# P02_Processor_1_of_3_JTAG_Header.net
KiCad netlist of a schematic drawn in Altium Designer
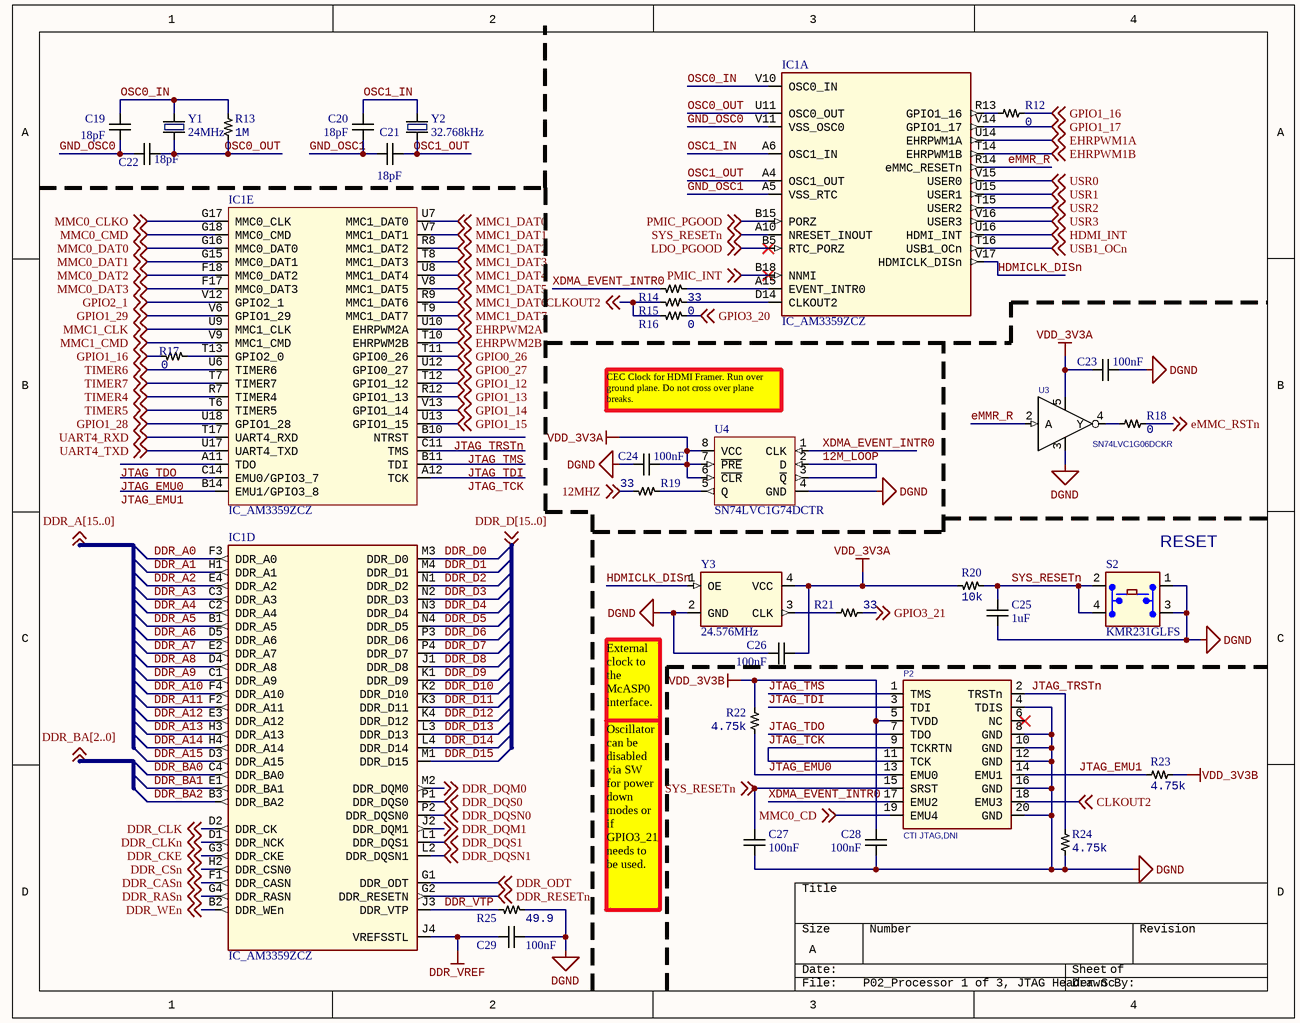
[diagram p0: P02_Processor 1 of 3, JTAG Header.SchDoc]

(export (version "E")
  (design (tool "Eeschema 10.0.6"))
  (components
    (comp (ref "C19")
      (value "CC0402JRNPO9BN180")
      (footprint "CAP0402")
      (description "MLCC 18pF 0402 SMD")
      (fields
        (field (name "MANUFACTURER") "Yageo")
        (field (name "CAPACITANCE") "18pF")
        (field (name "TOLERANCE") "5%")
      )
      (libsource (lib "Orient2") (part "CAP_18pF"))
    )
    (comp (ref "C20")
      (value "CC0402JRNPO9BN180")
      (footprint "CAP0402")
      (description "MLCC 18pF 0402 SMD")
      (fields
        (field (name "MANUFACTURER") "Yageo")
        (field (name "CAPACITANCE") "18pF")
        (field (name "TOLERANCE") "5%")
      )
      (libsource (lib "Orient2") (part "CAP_18pF"))
    )
    (comp (ref "C21")
      (value "CC0402JRNPO9BN180")
      (footprint "CAP0402")
      (description "MLCC 18pF 0402 SMD")
      (fields
        (field (name "MANUFACTURER") "Yageo")
        (field (name "CAPACITANCE") "18pF")
        (field (name "TOLERANCE") "5%")
      )
      (libsource (lib "Orient2") (part "CAP_18pF"))
    )
    (comp (ref "C22")
      (value "CC0402JRNPO9BN180")
      (footprint "CAP0402")
      (description "MLCC 18pF 0402 SMD")
      (fields
        (field (name "MANUFACTURER") "Yageo")
        (field (name "CAPACITANCE") "18pF")
        (field (name "TOLERANCE") "5%")
      )
      (libsource (lib "Orient2") (part "CAP_18pF"))
    )
    (comp (ref "C23")
      (value "C0402C104K4RACTU")
      (footprint "CAP0402")
      (description "MLCC 100nF 0402 SMD")
      (fields
        (field (name "MANUFACTURER") "KEMET")
        (field (name "TOLERANCE") "10%")
        (field (name "CAPACITANCE") "100nF")
      )
      (libsource (lib "Orient2") (part "CAP_100nF"))
    )
    (comp (ref "C24")
      (value "C0402C104K4RACTU")
      (footprint "CAP0402")
      (description "MLCC 100nF 0402 SMD")
      (fields
        (field (name "MANUFACTURER") "KEMET")
        (field (name "TOLERANCE") "10%")
        (field (name "CAPACITANCE") "100nF")
      )
      (libsource (lib "Orient2") (part "CAP_100nF"))
    )
    (comp (ref "C25")
      (value "CC0402KRX5R6BB105")
      (footprint "CAP0402")
      (description "MLCC 1uF 0402 SMD")
      (fields
        (field (name "CAPACITANCE") "1uF")
        (field (name "MANUFACTURER") "Yageo")
        (field (name "TOLERANCE") "10%")
      )
      (libsource (lib "Orient2") (part "CAP_1uF"))
    )
    (comp (ref "C26")
      (value "C0402C104K4RACTU")
      (footprint "CAP0402")
      (description "MLCC 100nF 0402 SMD")
      (fields
        (field (name "MANUFACTURER") "KEMET")
        (field (name "TOLERANCE") "10%")
        (field (name "CAPACITANCE") "100nF")
      )
      (libsource (lib "Orient2") (part "CAP_100nF"))
    )
    (comp (ref "C27")
      (value "C0402C104K4RACTU")
      (footprint "CAP0402")
      (description "MLCC 100nF 0402 SMD")
      (fields
        (field (name "MANUFACTURER") "KEMET")
        (field (name "TOLERANCE") "10%")
        (field (name "CAPACITANCE") "100nF")
      )
      (libsource (lib "Orient2") (part "CAP_100nF"))
    )
    (comp (ref "C28")
      (value "C0402C104K4RACTU")
      (footprint "CAP0402")
      (description "MLCC 100nF 0402 SMD")
      (fields
        (field (name "MANUFACTURER") "KEMET")
        (field (name "TOLERANCE") "10%")
        (field (name "CAPACITANCE") "100nF")
      )
      (libsource (lib "Orient2") (part "CAP_100nF"))
    )
    (comp (ref "C29")
      (value "C0402C104K4RACTU")
      (footprint "CAP0402")
      (description "MLCC 100nF 0402 SMD")
      (fields
        (field (name "MANUFACTURER") "KEMET")
        (field (name "TOLERANCE") "10%")
        (field (name "CAPACITANCE") "100nF")
      )
      (libsource (lib "Orient2") (part "CAP_100nF"))
    )
    (comp (ref "IC1")
      (value "IC_AM3359ZCZ")
      (footprint "BGA-324")
      (description "SubArctic Cortex A8 Processor 18x18")
      (fields
        (field (name "MANUFACTURER") "Texas Instruments")
        (field (name "MANUFACTURER PART NUMBER") "XAM3359ZCZ")
      )
      (libsource (lib "Orient2") (part "IC_AM335X_ZCE_1"))
    )
    (comp (ref "P2")
      (value "CTI JTAG,DNI")
      (description "Dual Line Header 10x2pin Tin")
      (fields
        (field (name "MANUFACTURER") "Samtec Inc")
        (field (name "MANUFACTURER PART NUMBER") "FTR-110-03-G-D-06")
      )
      (libsource (lib "Orient2") (part "HDR_10x2_CJTAG"))
    )
    (comp (ref "R12")
      (value "RC0402JR-070RL")
      (footprint "RES0402")
      (description "Resistor 0Ohm 0402 SMD")
      (fields
        (field (name "MANUFACTURER") "Yageo")
        (field (name "TOLERANCE") "5%")
        (field (name "RESISTANCE") "0")
      )
      (libsource (lib "Orient2") (part "RES_0"))
    )
    (comp (ref "R13")
      (value "RC0402FR-071ML")
      (footprint "RES0402")
      (description "Resistor 1MOhm 0402 SMD")
      (fields
        (field (name "MANUFACTURER") "Yageo")
        (field (name "TOLERANCE") "1%")
        (field (name "RESISTANCE") "1M")
      )
      (libsource (lib "Orient2") (part "RES_1M"))
    )
    (comp (ref "R14")
      (value "RC0402FR-0733RL")
      (footprint "RES0402")
      (description "Resistor 33Ohm 0402 SMD")
      (fields
        (field (name "MANUFACTURER") "Yageo")
        (field (name "TOLERANCE") "1%")
        (field (name "RESISTANCE") "33")
      )
      (libsource (lib "Orient2") (part "RES_33"))
    )
    (comp (ref "R15")
      (value "RC0402JR-070RL")
      (footprint "RES0402")
      (description "Resistor 0Ohm 0402 SMD")
      (fields
        (field (name "MANUFACTURER") "Yageo")
        (field (name "TOLERANCE") "5%")
        (field (name "RESISTANCE") "0")
      )
      (libsource (lib "Orient2") (part "RES_0"))
    )
    (comp (ref "R16")
      (value "RC0402JR-070RL")
      (footprint "RES0402")
      (description "Resistor 0Ohm 0402 SMD")
      (fields
        (field (name "MANUFACTURER") "Yageo")
        (field (name "TOLERANCE") "5%")
        (field (name "RESISTANCE") "0")
      )
      (libsource (lib "Orient2") (part "RES_0"))
    )
    (comp (ref "R17")
      (value "RC0402JR-070RL")
      (footprint "RES0402")
      (description "Resistor 0Ohm 0402 SMD")
      (fields
        (field (name "MANUFACTURER") "Yageo")
        (field (name "TOLERANCE") "5%")
        (field (name "RESISTANCE") "0")
      )
      (libsource (lib "Orient2") (part "RES_0"))
    )
    (comp (ref "R18")
      (value "RC0402JR-070RL")
      (footprint "RES0402")
      (description "Resistor 0Ohm 0402 SMD")
      (fields
        (field (name "MANUFACTURER") "Yageo")
        (field (name "TOLERANCE") "5%")
        (field (name "RESISTANCE") "0")
      )
      (libsource (lib "Orient2") (part "RES_0"))
    )
    (comp (ref "R19")
      (value "RC0402FR-0733RL")
      (footprint "RES0402")
      (description "Resistor 33Ohm 0402 SMD")
      (fields
        (field (name "MANUFACTURER") "Yageo")
        (field (name "TOLERANCE") "1%")
        (field (name "RESISTANCE") "33")
      )
      (libsource (lib "Orient2") (part "RES_33"))
    )
    (comp (ref "R20")
      (value "RC0402FR-0710KL")
      (footprint "RES0402")
      (description "Resistor 10kOhm 0402 SMD")
      (fields
        (field (name "MANUFACTURER") "Yageo")
        (field (name "TOLERANCE") "1%")
        (field (name "RESISTANCE") "10k")
      )
      (libsource (lib "Orient2") (part "RES_10k"))
    )
    (comp (ref "R21")
      (value "RC0402FR-0733RL")
      (footprint "RES0402")
      (description "Resistor 33Ohm 0402 SMD")
      (fields
        (field (name "MANUFACTURER") "Yageo")
        (field (name "TOLERANCE") "1%")
        (field (name "RESISTANCE") "33")
      )
      (libsource (lib "Orient2") (part "RES_33"))
    )
    (comp (ref "R22")
      (value "RC0402FR-074K75L")
      (footprint "RES0402")
      (description "Resistor 4.75kOhm 0402 SMD")
      (fields
        (field (name "MANUFACTURER") "Yageo")
        (field (name "TOLERANCE") "1%")
        (field (name "RESISTANCE") "4.75k")
      )
      (libsource (lib "Orient2") (part "RES_4.75k"))
    )
    (comp (ref "R23")
      (value "RC0402FR-074K75L")
      (footprint "RES0402")
      (description "Resistor 4.75kOhm 0402 SMD")
      (fields
        (field (name "MANUFACTURER") "Yageo")
        (field (name "TOLERANCE") "1%")
        (field (name "RESISTANCE") "4.75k")
      )
      (libsource (lib "Orient2") (part "RES_4.75k"))
    )
    (comp (ref "R24")
      (value "RC0402FR-074K75L")
      (footprint "RES0402")
      (description "Resistor 4.75kOhm 0402 SMD")
      (fields
        (field (name "MANUFACTURER") "Yageo")
        (field (name "TOLERANCE") "1%")
        (field (name "RESISTANCE") "4.75k")
      )
      (libsource (lib "Orient2") (part "RES_4.75k"))
    )
    (comp (ref "R25")
      (value "RC0402FR-0749R9")
      (footprint "RES0402")
      (description "Resistor 49.9Ohm 0402 SMD")
      (fields
        (field (name "MANUFACTURER") "Yageo")
        (field (name "MANUFACTURER PART NUMBER") "RC0402FR-0749R9L")
        (field (name "RESISTANCE") "49.9")
      )
      (libsource (lib "Orient2") (part "RES_49.9"))
    )
    (comp (ref "S2")
      (value "KMR231GLFS")
      (footprint "SW4SMD_63X161LS")
      (description "Microminiature Tact Switch for SMT")
      (fields (field (name "MANUFACTURER") "C&K Components"))
      (libsource (lib "Orient2") (part "KMR2"))
    )
    (comp (ref "U3")
      (value "SN74LVC1G06DCKR")
      (footprint "SC70_DCK")
      (description "IC INVERTER SINGLE 1INPUT SC705")
      (fields
        (field (name "MANUFACTURER") "Texas Instruments")
        (field (name "MANUFACTURER PART NUMBER") "SN74LVC1G06DCKTG4")
      )
      (libsource (lib "Orient2") (part "IC_Inverter"))
    )
    (comp (ref "U4")
      (value "SN74LVC1G74DCTR")
      (footprint "VSSOP-8")
      (description "SINGLE  POSITIVE-EDGE-TRIGGERED  D-TYPE  FLIP-FLOP WITH  CLEAR  AND  PRESET")
      (fields (field (name "MANUFACTURER") "Texas Instruments"))
      (libsource (lib "Orient2") (part "SN74LVC1G74DCTR"))
    )
    (comp (ref "Y1")
      (value "24MHz")
      (footprint "XTAL150SMD_125X196")
      (description "CRYSTAL 24.000MHZ 18PF SMD")
      (fields
        (field (name "MANUFACTURER") "TXC CORPORATION")
        (field (name "MANUFACTURER PART NUMBER") "7A-24.000MAAJ-T")
      )
      (libsource (lib "Orient2") (part "CRYS_24MHz_SCC"))
    )
    (comp (ref "Y2")
      (value "32.768kHz")
      (footprint "SOJ-4")
      (description "CRYSTAL 32.768KHZ 12.5PF SMD")
      (fields
        (field (name "MANUFACTURER") "Citizen Finetech Miyota")
        (field (name "MANUFACTURER PART NUMBER") "CM200C-32.768KAZF-UT")
      )
      (libsource (lib "Orient2") (part "CRYS_32.768kHz"))
    )
    (comp (ref "Y3")
      (value "24.576MHz")
      (footprint "OSC4_61X65LS_79X98SMD")
      (fields
        (field (name "MANUFACTURER") "Abracon Corporation")
        (field (name "MANUFACTURER PART NUMBER") "ASDMB-24.576MHZ-LC-T")
      )
      (libsource (lib "Orient2") (part "ASDMB"))
    )
  )
  (nets
    (net (code "1") (name "/12M_LOOP") (class "Default")
      (node (ref "U4") (pin "2") (pinfunction "D_2") (pintype "input"))
      (node (ref "U4") (pin "3") (pinfunction "~{Q}_3") (pintype "output"))
    )
    (net (code "2") (name "/DDR_VTP") (class "Default")
      (node (ref "IC1") (pin "J3") (pinfunction "DDR_VTP_J3") (pintype "passive"))
      (node (ref "R25") (pin "2") (pintype "passive"))
    )
    (net (code "3") (name "/GND_OSC0") (class "Default")
      (node (ref "C19") (pin "2") (pintype "passive"))
      (node (ref "C22") (pin "1") (pintype "passive"))
      (node (ref "IC1") (pin "V11") (pinfunction "VSS_OSC0_V11") (pintype "power_in"))
    )
    (net (code "4") (name "/GND_OSC1") (class "Default")
      (node (ref "C20") (pin "1") (pintype "passive"))
      (node (ref "C21") (pin "2") (pintype "passive"))
      (node (ref "IC1") (pin "A5") (pinfunction "VSS_RTC_A5") (pintype "power_in"))
    )
    (net (code "5") (name "/HDMICLK_DISn") (class "Default")
      (node (ref "IC1") (pin "V17") (pinfunction "HDMICLK_DISn_V17") (pintype "output"))
      (node (ref "Y3") (pin "1") (pinfunction "OE_1") (pintype "input"))
    )
    (net (code "6") (name "/JTAG_EMU0") (class "Default")
      (node (ref "IC1") (pin "C14") (pinfunction "EMU0/GPIO3_7_C14") (pintype "passive"))
      (node (ref "P2") (pin "13") (pinfunction "EMU0_13") (pintype "passive"))
      (node (ref "R22") (pin "1") (pintype "passive"))
    )
    (net (code "7") (name "/JTAG_EMU1") (class "Default")
      (node (ref "IC1") (pin "B14") (pinfunction "EMU1/GPIO3_8_B14") (pintype "passive"))
      (node (ref "P2") (pin "14") (pinfunction "EMU1_14") (pintype "passive"))
      (node (ref "R23") (pin "2") (pintype "passive"))
    )
    (net (code "8") (name "/JTAG_TCK") (class "Default")
      (node (ref "IC1") (pin "A12") (pinfunction "TCK_A12") (pintype "passive"))
      (node (ref "P2") (pin "11") (pinfunction "TCK_11") (pintype "passive"))
      (node (ref "P2") (pin "9") (pinfunction "TCKRTN_9") (pintype "passive"))
    )
    (net (code "9") (name "/JTAG_TDI") (class "Default")
      (node (ref "IC1") (pin "B11") (pinfunction "TDI_B11") (pintype "passive"))
      (node (ref "P2") (pin "3") (pinfunction "TDI_3") (pintype "passive"))
    )
    (net (code "10") (name "/JTAG_TDO") (class "Default")
      (node (ref "IC1") (pin "A11") (pinfunction "TDO_A11") (pintype "passive"))
      (node (ref "P2") (pin "7") (pinfunction "TDO_7") (pintype "passive"))
    )
    (net (code "11") (name "/JTAG_TMS") (class "Default")
      (node (ref "IC1") (pin "C11") (pinfunction "TMS_C11") (pintype "passive"))
      (node (ref "P2") (pin "1") (pinfunction "TMS_1") (pintype "passive"))
    )
    (net (code "12") (name "/JTAG_TRSTn") (class "Default")
      (node (ref "IC1") (pin "B10") (pinfunction "NTRST_B10") (pintype "passive"))
      (node (ref "P2") (pin "2") (pinfunction "TRSTn_2") (pintype "passive"))
      (node (ref "R24") (pin "2") (pintype "passive"))
    )
    (net (code "13") (name "/OSC0_IN") (class "Default")
      (node (ref "C19") (pin "1") (pintype "passive"))
      (node (ref "IC1") (pin "V10") (pinfunction "OSC0_IN_V10") (pintype "passive"))
      (node (ref "R13") (pin "2") (pintype "passive"))
      (node (ref "Y1") (pin "4") (pinfunction "4_4") (pintype "passive"))
    )
    (net (code "14") (name "/OSC0_OUT") (class "Default")
      (node (ref "C22") (pin "2") (pintype "passive"))
      (node (ref "IC1") (pin "U11") (pinfunction "OSC0_OUT_U11") (pintype "passive"))
      (node (ref "R13") (pin "1") (pintype "passive"))
      (node (ref "Y1") (pin "1") (pinfunction "1_1") (pintype "passive"))
    )
    (net (code "15") (name "/OSC1_IN") (class "Default")
      (node (ref "C20") (pin "2") (pintype "passive"))
      (node (ref "IC1") (pin "A6") (pinfunction "OSC1_IN_A6") (pintype "passive"))
      (node (ref "Y2") (pin "1") (pinfunction "1_1") (pintype "passive"))
    )
    (net (code "16") (name "/OSC1_OUT") (class "Default")
      (node (ref "C21") (pin "1") (pintype "passive"))
      (node (ref "IC1") (pin "A4") (pinfunction "OSC1_OUT_A4") (pintype "passive"))
      (node (ref "Y2") (pin "4") (pinfunction "4_4") (pintype "passive"))
    )
    (net (code "17") (name "/XDMA_EVENT_INTR0") (class "Default")
      (node (ref "P2") (pin "17") (pinfunction "EMU2_17") (pintype "passive"))
      (node (ref "R14") (pin "1") (pintype "passive"))
      (node (ref "U4") (pin "1") (pinfunction "CLK_1") (pintype "input"))
    )
    (net (code "18") (name "/eMMR_R") (class "Default")
      (node (ref "IC1") (pin "R14") (pinfunction "eMMC_RESETn_R14") (pintype "output"))
      (node (ref "U3") (pin "2") (pinfunction "A_2") (pintype "input"))
    )
    (net (code "19") (name "12MHZ") (class "Default") (node (ref "R19") (pin "1") (pintype "passive")))
    (net (code "20") (name "CLKOUT2") (class "Default")
      (node (ref "P2") (pin "18") (pinfunction "EMU3_18") (pintype "passive"))
      (node (ref "R15") (pin "2") (pintype "passive"))
      (node (ref "R16") (pin "2") (pintype "passive"))
    )
    (net (code "21") (name "DDR_A0") (class "Default")
      (node (ref "IC1") (pin "F3") (pinfunction "DDR_A0_F3") (pintype "output"))
    )
    (net (code "22") (name "DDR_A1") (class "Default")
      (node (ref "IC1") (pin "H1") (pinfunction "DDR_A1_H1") (pintype "output"))
    )
    (net (code "23") (name "DDR_A2") (class "Default")
      (node (ref "IC1") (pin "E4") (pinfunction "DDR_A2_E4") (pintype "output"))
    )
    (net (code "24") (name "DDR_A3") (class "Default")
      (node (ref "IC1") (pin "C3") (pinfunction "DDR_A3_C3") (pintype "output"))
    )
    (net (code "25") (name "DDR_A4") (class "Default")
      (node (ref "IC1") (pin "C2") (pinfunction "DDR_A4_C2") (pintype "output"))
    )
    (net (code "26") (name "DDR_A5") (class "Default")
      (node (ref "IC1") (pin "B1") (pinfunction "DDR_A5_B1") (pintype "output"))
    )
    (net (code "27") (name "DDR_A6") (class "Default")
      (node (ref "IC1") (pin "D5") (pinfunction "DDR_A6_D5") (pintype "output"))
    )
    (net (code "28") (name "DDR_A7") (class "Default")
      (node (ref "IC1") (pin "E2") (pinfunction "DDR_A7_E2") (pintype "output"))
    )
    (net (code "29") (name "DDR_A8") (class "Default")
      (node (ref "IC1") (pin "D4") (pinfunction "DDR_A8_D4") (pintype "output"))
    )
    (net (code "30") (name "DDR_A9") (class "Default")
      (node (ref "IC1") (pin "C1") (pinfunction "DDR_A9_C1") (pintype "output"))
    )
    (net (code "31") (name "DDR_A10") (class "Default")
      (node (ref "IC1") (pin "F4") (pinfunction "DDR_A10_F4") (pintype "output"))
    )
    (net (code "32") (name "DDR_A11") (class "Default")
      (node (ref "IC1") (pin "F2") (pinfunction "DDR_A11_F2") (pintype "output"))
    )
    (net (code "33") (name "DDR_A12") (class "Default")
      (node (ref "IC1") (pin "E3") (pinfunction "DDR_A12_E3") (pintype "output"))
    )
    (net (code "34") (name "DDR_A13") (class "Default")
      (node (ref "IC1") (pin "H3") (pinfunction "DDR_A13_H3") (pintype "output"))
    )
    (net (code "35") (name "DDR_A14") (class "Default")
      (node (ref "IC1") (pin "H4") (pinfunction "DDR_A14_H4") (pintype "output"))
    )
    (net (code "36") (name "DDR_A15") (class "Default")
      (node (ref "IC1") (pin "D3") (pinfunction "DDR_A15_D3") (pintype "output"))
    )
    (net (code "38") (name "DDR_BA0") (class "Default")
      (node (ref "IC1") (pin "C4") (pinfunction "DDR_BA0_C4") (pintype "output"))
    )
    (net (code "39") (name "DDR_BA1") (class "Default")
      (node (ref "IC1") (pin "E1") (pinfunction "DDR_BA1_E1") (pintype "output"))
    )
    (net (code "40") (name "DDR_BA2") (class "Default")
      (node (ref "IC1") (pin "B3") (pinfunction "DDR_BA2_B3") (pintype "output"))
    )
    (net (code "42") (name "DDR_CASn") (class "Default")
      (node (ref "IC1") (pin "F1") (pinfunction "DDR_CASN_F1") (pintype "output"))
    )
    (net (code "43") (name "DDR_CKE") (class "Default")
      (node (ref "IC1") (pin "G3") (pinfunction "DDR_CKE_G3") (pintype "output"))
    )
    (net (code "44") (name "DDR_CLK") (class "Default")
      (node (ref "IC1") (pin "D2") (pinfunction "DDR_CK_D2") (pintype "output"))
    )
    (net (code "45") (name "DDR_CLKn") (class "Default")
      (node (ref "IC1") (pin "D1") (pinfunction "DDR_NCK_D1") (pintype "output"))
    )
    (net (code "46") (name "DDR_CSn") (class "Default")
      (node (ref "IC1") (pin "H2") (pinfunction "DDR_CSN0_H2") (pintype "output"))
    )
    (net (code "47") (name "DDR_D0") (class "Default")
      (node (ref "IC1") (pin "M3") (pinfunction "DDR_D0_M3") (pintype "bidirectional"))
    )
    (net (code "48") (name "DDR_D1") (class "Default")
      (node (ref "IC1") (pin "M4") (pinfunction "DDR_D1_M4") (pintype "bidirectional"))
    )
    (net (code "49") (name "DDR_D2") (class "Default")
      (node (ref "IC1") (pin "N1") (pinfunction "DDR_D2_N1") (pintype "bidirectional"))
    )
    (net (code "50") (name "DDR_D3") (class "Default")
      (node (ref "IC1") (pin "N2") (pinfunction "DDR_D3_N2") (pintype "bidirectional"))
    )
    (net (code "51") (name "DDR_D4") (class "Default")
      (node (ref "IC1") (pin "N3") (pinfunction "DDR_D4_N3") (pintype "bidirectional"))
    )
    (net (code "52") (name "DDR_D5") (class "Default")
      (node (ref "IC1") (pin "N4") (pinfunction "DDR_D5_N4") (pintype "bidirectional"))
    )
    (net (code "53") (name "DDR_D6") (class "Default")
      (node (ref "IC1") (pin "P3") (pinfunction "DDR_D6_P3") (pintype "bidirectional"))
    )
    (net (code "54") (name "DDR_D7") (class "Default")
      (node (ref "IC1") (pin "P4") (pinfunction "DDR_D7_P4") (pintype "bidirectional"))
    )
    (net (code "55") (name "DDR_D8") (class "Default")
      (node (ref "IC1") (pin "J1") (pinfunction "DDR_D8_J1") (pintype "bidirectional"))
    )
    (net (code "56") (name "DDR_D9") (class "Default")
      (node (ref "IC1") (pin "K1") (pinfunction "DDR_D9_K1") (pintype "bidirectional"))
    )
    (net (code "57") (name "DDR_D10") (class "Default")
      (node (ref "IC1") (pin "K2") (pinfunction "DDR_D10_K2") (pintype "bidirectional"))
    )
    (net (code "58") (name "DDR_D11") (class "Default")
      (node (ref "IC1") (pin "K3") (pinfunction "DDR_D11_K3") (pintype "bidirectional"))
    )
    (net (code "59") (name "DDR_D12") (class "Default")
      (node (ref "IC1") (pin "K4") (pinfunction "DDR_D12_K4") (pintype "bidirectional"))
    )
    (net (code "60") (name "DDR_D13") (class "Default")
      (node (ref "IC1") (pin "L3") (pinfunction "DDR_D13_L3") (pintype "bidirectional"))
    )
    (net (code "61") (name "DDR_D14") (class "Default")
      (node (ref "IC1") (pin "L4") (pinfunction "DDR_D14_L4") (pintype "bidirectional"))
    )
    (net (code "62") (name "DDR_D15") (class "Default")
      (node (ref "IC1") (pin "M1") (pinfunction "DDR_D15_M1") (pintype "bidirectional"))
    )
    (net (code "63") (name "DDR_DQM0") (class "Default")
      (node (ref "IC1") (pin "M2") (pinfunction "DDR_DQM0_M2") (pintype "output"))
    )
    (net (code "64") (name "DDR_DQM1") (class "Default")
      (node (ref "IC1") (pin "J2") (pinfunction "DDR_DQM1_J2") (pintype "output"))
    )
    (net (code "65") (name "DDR_DQS0") (class "Default")
      (node (ref "IC1") (pin "P1") (pinfunction "DDR_DQS0_P1") (pintype "bidirectional"))
    )
    (net (code "66") (name "DDR_DQS1") (class "Default")
      (node (ref "IC1") (pin "L1") (pinfunction "DDR_DQS1_L1") (pintype "bidirectional"))
    )
    (net (code "67") (name "DDR_DQSN0") (class "Default")
      (node (ref "IC1") (pin "P2") (pinfunction "DDR_DQSN0_P2") (pintype "bidirectional"))
    )
    (net (code "68") (name "DDR_DQSN1") (class "Default")
      (node (ref "IC1") (pin "L2") (pinfunction "DDR_DQSN1_L2") (pintype "bidirectional"))
    )
    (net (code "70") (name "DDR_ODT") (class "Default")
      (node (ref "IC1") (pin "G1") (pinfunction "DDR_ODT_G1") (pintype "passive"))
    )
    (net (code "71") (name "DDR_RASn") (class "Default")
      (node (ref "IC1") (pin "G4") (pinfunction "DDR_RASN_G4") (pintype "output"))
    )
    (net (code "72") (name "DDR_RESETn") (class "Default")
      (node (ref "IC1") (pin "G2") (pinfunction "DDR_RESETN_G2") (pintype "output"))
    )
    (net (code "73") (name "DDR_VREF") (class "Default")
      (node (ref "C29") (pin "1") (pintype "passive"))
      (node (ref "IC1") (pin "J4") (pinfunction "VREFSSTL_J4") (pintype "passive"))
    )
    (net (code "74") (name "DDR_WEn") (class "Default")
      (node (ref "IC1") (pin "B2") (pinfunction "DDR_WEn_B2") (pintype "output"))
    )
    (net (code "75") (name "DGND") (class "Default")
      (node (ref "C23") (pin "1") (pintype "passive"))
      (node (ref "C24") (pin "1") (pintype "passive"))
      (node (ref "C25") (pin "1") (pintype "passive"))
      (node (ref "C26") (pin "1") (pintype "passive"))
      (node (ref "C27") (pin "2") (pintype "passive"))
      (node (ref "C28") (pin "2") (pintype "passive"))
      (node (ref "C29") (pin "2") (pintype "passive"))
      (node (ref "P2") (pin "10") (pinfunction "GND_10") (pintype "power_in"))
      (node (ref "P2") (pin "12") (pinfunction "GND_12") (pintype "power_in"))
      (node (ref "P2") (pin "16") (pinfunction "GND_16") (pintype "power_in"))
      (node (ref "P2") (pin "20") (pinfunction "GND_20") (pintype "power_in"))
      (node (ref "P2") (pin "4") (pinfunction "TDIS_4") (pintype "passive"))
      (node (ref "P2") (pin "8") (pinfunction "GND_8") (pintype "power_in"))
      (node (ref "R24") (pin "1") (pintype "passive"))
      (node (ref "R25") (pin "1") (pintype "passive"))
      (node (ref "S2") (pin "1") (pinfunction "A1_1") (pintype "passive"))
      (node (ref "S2") (pin "3") (pinfunction "A3_3") (pintype "passive"))
      (node (ref "U3") (pin "3") (pinfunction "GND_3") (pintype "power_in"))
      (node (ref "U4") (pin "4") (pinfunction "GND_4") (pintype "power_in"))
      (node (ref "Y3") (pin "2") (pinfunction "GND_2") (pintype "power_in"))
    )
    (net (code "76") (name "EHRPWM1A") (class "Default")
      (node (ref "IC1") (pin "U14") (pinfunction "EHRPWM1A_U14") (pintype "output"))
    )
    (net (code "77") (name "EHRPWM1B") (class "Default")
      (node (ref "IC1") (pin "T14") (pinfunction "EHRPWM1B_T14") (pintype "output"))
    )
    (net (code "78") (name "EHRPWM2A") (class "Default")
      (node (ref "IC1") (pin "U10") (pinfunction "EHRPWM2A_U10") (pintype "bidirectional"))
    )
    (net (code "79") (name "EHRPWM2B") (class "Default")
      (node (ref "IC1") (pin "T10") (pinfunction "EHRPWM2B_T10") (pintype "bidirectional"))
    )
    (net (code "80") (name "GPIO0_26") (class "Default")
      (node (ref "IC1") (pin "T11") (pinfunction "GPIO0_26_T11") (pintype "bidirectional"))
    )
    (net (code "81") (name "GPIO0_27") (class "Default")
      (node (ref "IC1") (pin "U12") (pinfunction "GPIO0_27_U12") (pintype "bidirectional"))
    )
    (net (code "82") (name "GPIO1_12") (class "Default")
      (node (ref "IC1") (pin "T12") (pinfunction "GPIO1_12_T12") (pintype "bidirectional"))
    )
    (net (code "83") (name "GPIO1_13") (class "Default")
      (node (ref "IC1") (pin "R12") (pinfunction "GPIO1_13_R12") (pintype "bidirectional"))
    )
    (net (code "84") (name "GPIO1_14") (class "Default")
      (node (ref "IC1") (pin "V13") (pinfunction "GPIO1_14_V13") (pintype "bidirectional"))
    )
    (net (code "85") (name "GPIO1_15") (class "Default")
      (node (ref "IC1") (pin "U13") (pinfunction "GPIO1_15_U13") (pintype "bidirectional"))
    )
    (net (code "86") (name "GPIO1_16") (class "Default")
      (node (ref "R12") (pin "2") (pintype "passive"))
      (node (ref "R17") (pin "2") (pintype "passive"))
    )
    (net (code "87") (name "GPIO1_17") (class "Default")
      (node (ref "IC1") (pin "V14") (pinfunction "GPIO1_17_V14") (pintype "output"))
    )
    (net (code "88") (name "GPIO1_28") (class "Default")
      (node (ref "IC1") (pin "U18") (pinfunction "GPIO1_28_U18") (pintype "bidirectional"))
    )
    (net (code "89") (name "GPIO1_29") (class "Default")
      (node (ref "IC1") (pin "V6") (pinfunction "GPIO1_29_V6") (pintype "bidirectional"))
    )
    (net (code "90") (name "GPIO2_1") (class "Default")
      (node (ref "IC1") (pin "V12") (pinfunction "GPIO2_1_V12") (pintype "bidirectional"))
    )
    (net (code "91") (name "GPIO3_20") (class "Default") (node (ref "R16") (pin "1") (pintype "passive")))
    (net (code "92") (name "GPIO3_21") (class "Default") (node (ref "R21") (pin "2") (pintype "passive")))
    (net (code "93") (name "HDMI_INT") (class "Default")
      (node (ref "IC1") (pin "U16") (pinfunction "HDMI_INT_U16") (pintype "output"))
    )
    (net (code "94") (name "LDO_PGOOD") (class "Default")
      (node (ref "IC1") (pin "B5") (pinfunction "RTC_PORZ_B5") (pintype "input"))
    )
    (net (code "95") (name "MMC0_CD") (class "Default")
      (node (ref "P2") (pin "19") (pinfunction "EMU4_19") (pintype "passive"))
    )
    (net (code "96") (name "MMC0_CLKO") (class "Default")
      (node (ref "IC1") (pin "G17") (pinfunction "MMC0_CLK_G17") (pintype "bidirectional"))
    )
    (net (code "97") (name "MMC0_CMD") (class "Default")
      (node (ref "IC1") (pin "G18") (pinfunction "MMC0_CMD_G18") (pintype "bidirectional"))
    )
    (net (code "98") (name "MMC0_DAT0") (class "Default")
      (node (ref "IC1") (pin "G16") (pinfunction "MMC0_DAT0_G16") (pintype "bidirectional"))
    )
    (net (code "99") (name "MMC0_DAT1") (class "Default")
      (node (ref "IC1") (pin "G15") (pinfunction "MMC0_DAT1_G15") (pintype "bidirectional"))
    )
    (net (code "100") (name "MMC0_DAT2") (class "Default")
      (node (ref "IC1") (pin "F18") (pinfunction "MMC0_DAT2_F18") (pintype "bidirectional"))
    )
    (net (code "101") (name "MMC0_DAT3") (class "Default")
      (node (ref "IC1") (pin "F17") (pinfunction "MMC0_DAT3_F17") (pintype "bidirectional"))
    )
    (net (code "102") (name "MMC1_CLK") (class "Default")
      (node (ref "IC1") (pin "U9") (pinfunction "MMC1_CLK_U9") (pintype "bidirectional"))
    )
    (net (code "103") (name "MMC1_CMD") (class "Default")
      (node (ref "IC1") (pin "V9") (pinfunction "MMC1_CMD_V9") (pintype "bidirectional"))
    )
    (net (code "104") (name "MMC1_DAT0") (class "Default")
      (node (ref "IC1") (pin "U7") (pinfunction "MMC1_DAT0_U7") (pintype "bidirectional"))
    )
    (net (code "105") (name "MMC1_DAT1") (class "Default")
      (node (ref "IC1") (pin "V7") (pinfunction "MMC1_DAT1_V7") (pintype "bidirectional"))
    )
    (net (code "106") (name "MMC1_DAT2") (class "Default")
      (node (ref "IC1") (pin "R8") (pinfunction "MMC1_DAT2_R8") (pintype "bidirectional"))
    )
    (net (code "107") (name "MMC1_DAT3") (class "Default")
      (node (ref "IC1") (pin "T8") (pinfunction "MMC1_DAT3_T8") (pintype "bidirectional"))
    )
    (net (code "108") (name "MMC1_DAT4") (class "Default")
      (node (ref "IC1") (pin "U8") (pinfunction "MMC1_DAT4_U8") (pintype "bidirectional"))
    )
    (net (code "109") (name "MMC1_DAT5") (class "Default")
      (node (ref "IC1") (pin "V8") (pinfunction "MMC1_DAT5_V8") (pintype "bidirectional"))
    )
    (net (code "110") (name "MMC1_DAT6") (class "Default")
      (node (ref "IC1") (pin "R9") (pinfunction "MMC1_DAT6_R9") (pintype "bidirectional"))
    )
    (net (code "111") (name "MMC1_DAT7") (class "Default")
      (node (ref "IC1") (pin "T9") (pinfunction "MMC1_DAT7_T9") (pintype "bidirectional"))
    )
    (net (code "112") (name "Net-(IC1A-CLKOUT2)") (class "Default")
      (node (ref "IC1") (pin "D14") (pinfunction "CLKOUT2_D14") (pintype "bidirectional"))
      (node (ref "R15") (pin "1") (pintype "passive"))
    )
    (net (code "113") (name "Net-(IC1A-EVENT_INTR0)") (class "Default")
      (node (ref "IC1") (pin "A15") (pinfunction "EVENT_INTR0_A15") (pintype "bidirectional"))
      (node (ref "R14") (pin "2") (pintype "passive"))
    )
    (net (code "114") (name "Net-(IC1A-GPIO1_16)") (class "Default")
      (node (ref "IC1") (pin "R13") (pinfunction "GPIO1_16_R13") (pintype "output"))
      (node (ref "R12") (pin "1") (pintype "passive"))
    )
    (net (code "115") (name "Net-(IC1E-GPIO2_0)") (class "Default")
      (node (ref "IC1") (pin "T13") (pinfunction "GPIO2_0_T13") (pintype "bidirectional"))
      (node (ref "R17") (pin "1") (pintype "passive"))
    )
    (net (code "116") (name "Net-(U3-Y)") (class "Default")
      (node (ref "R18") (pin "1") (pintype "passive"))
      (node (ref "U3") (pin "4") (pinfunction "Y_4") (pintype "open_collector"))
    )
    (net (code "117") (name "Net-(U4-Q)") (class "Default")
      (node (ref "R19") (pin "2") (pintype "passive"))
      (node (ref "U4") (pin "5") (pinfunction "Q_5") (pintype "output"))
    )
    (net (code "118") (name "Net-(Y3-CLK)") (class "Default")
      (node (ref "R21") (pin "1") (pintype "passive"))
      (node (ref "Y3") (pin "3") (pinfunction "CLK_3") (pintype "output"))
    )
    (net (code "119") (name "PMIC_INT") (class "Default")
      (node (ref "IC1") (pin "B18") (pinfunction "NNMI_B18") (pintype "input"))
    )
    (net (code "120") (name "PMIC_PGOOD") (class "Default")
      (node (ref "IC1") (pin "B15") (pinfunction "PORZ_B15") (pintype "input"))
    )
    (net (code "121") (name "SYS_RESETn") (class "Default")
      (node (ref "C25") (pin "2") (pintype "passive"))
      (node (ref "C27") (pin "1") (pintype "passive"))
      (node (ref "IC1") (pin "A10") (pinfunction "NRESET_INOUT_A10") (pintype "bidirectional"))
      (node (ref "P2") (pin "15") (pinfunction "SRST_15") (pintype "passive"))
      (node (ref "R20") (pin "2") (pintype "passive"))
      (node (ref "S2") (pin "2") (pinfunction "A2_2") (pintype "passive"))
      (node (ref "S2") (pin "4") (pinfunction "4_4") (pintype "power_in"))
    )
    (net (code "122") (name "TIMER4") (class "Default")
      (node (ref "IC1") (pin "R7") (pinfunction "TIMER4_R7") (pintype "bidirectional"))
    )
    (net (code "123") (name "TIMER5") (class "Default")
      (node (ref "IC1") (pin "T6") (pinfunction "TIMER5_T6") (pintype "bidirectional"))
    )
    (net (code "124") (name "TIMER6") (class "Default")
      (node (ref "IC1") (pin "U6") (pinfunction "TIMER6_U6") (pintype "bidirectional"))
    )
    (net (code "125") (name "TIMER7") (class "Default")
      (node (ref "IC1") (pin "T7") (pinfunction "TIMER7_T7") (pintype "bidirectional"))
    )
    (net (code "126") (name "UART4_RXD") (class "Default")
      (node (ref "IC1") (pin "T17") (pinfunction "UART4_RXD_T17") (pintype "bidirectional"))
    )
    (net (code "127") (name "UART4_TXD") (class "Default")
      (node (ref "IC1") (pin "U17") (pinfunction "UART4_TXD_U17") (pintype "bidirectional"))
    )
    (net (code "128") (name "USB1_OCn") (class "Default")
      (node (ref "IC1") (pin "T16") (pinfunction "USB1_OCn_T16") (pintype "output"))
    )
    (net (code "129") (name "USR0") (class "Default")
      (node (ref "IC1") (pin "V15") (pinfunction "USER0_V15") (pintype "output"))
    )
    (net (code "130") (name "USR1") (class "Default")
      (node (ref "IC1") (pin "U15") (pinfunction "USER1_U15") (pintype "output"))
    )
    (net (code "131") (name "USR2") (class "Default")
      (node (ref "IC1") (pin "T15") (pinfunction "USER2_T15") (pintype "output"))
    )
    (net (code "132") (name "USR3") (class "Default")
      (node (ref "IC1") (pin "V16") (pinfunction "USER3_V16") (pintype "output"))
    )
    (net (code "133") (name "VDD_3V3A") (class "Default")
      (node (ref "C23") (pin "2") (pintype "passive"))
      (node (ref "C24") (pin "2") (pintype "passive"))
      (node (ref "C26") (pin "2") (pintype "passive"))
      (node (ref "R20") (pin "1") (pintype "passive"))
      (node (ref "U3") (pin "5") (pinfunction "VCC_5") (pintype "power_in"))
      (node (ref "U4") (pin "6") (pinfunction "~{CLR}_6") (pintype "input"))
      (node (ref "U4") (pin "7") (pinfunction "~{PRE}_7") (pintype "input"))
      (node (ref "U4") (pin "8") (pinfunction "VCC_8") (pintype "power_in"))
      (node (ref "Y3") (pin "4") (pinfunction "VCC_4") (pintype "power_in"))
    )
    (net (code "134") (name "VDD_3V3B") (class "Default")
      (node (ref "C28") (pin "1") (pintype "passive"))
      (node (ref "P2") (pin "5") (pinfunction "TVDD_5") (pintype "passive"))
      (node (ref "R22") (pin "2") (pintype "passive"))
      (node (ref "R23") (pin "1") (pintype "passive"))
    )
    (net (code "135") (name "eMMC_RSTn") (class "Default") (node (ref "R18") (pin "2") (pintype "passive")))
    (net (code "136") (name "unconnected-(P2-NC-Pad6)") (class "Default")
      (node (ref "P2") (pin "6") (pinfunction "NC_6") (pintype "passive+no_connect"))
    )
  )
)
